# PX4FMUv2_4_6_6.net
KiCad netlist of a schematic drawn in Altium Designer
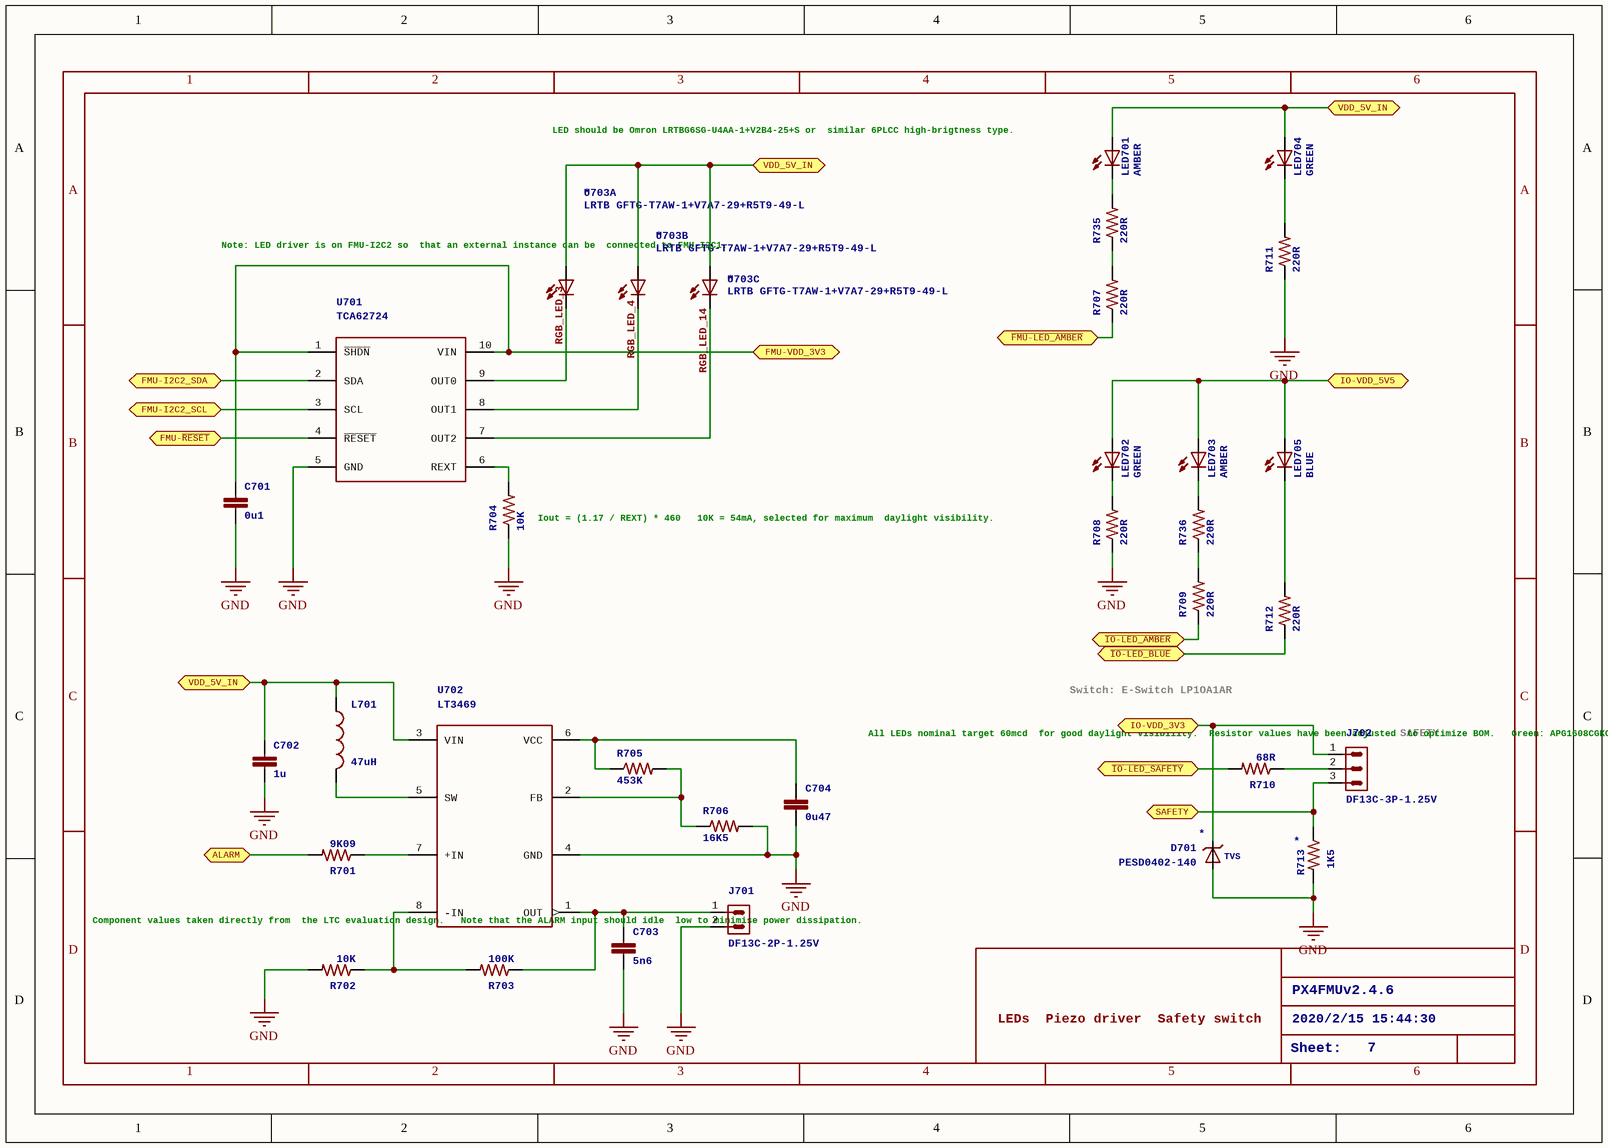
[diagram p0: PX4FMUv2.4.6_6.SchDoc]

(export (version "E")
  (design (tool "Eeschema 10.0.6"))
  (components
    (comp (ref "C701")
      (value "0u1")
      (footprint "0402-CAP")
      (description "CapacitorStandard 0603 ceramic capacitor, and 0.1\" leaded capacitor.")
      (fields (field (name "PARTNO") "CC0402ZRY5V7BB104"))
      (libsource (lib "pixhawk2") (part "CAP0402"))
    )
    (comp (ref "C702")
      (value "1u")
      (footprint "0603-CAP")
      (description "CapacitorStandard 0603 ceramic capacitor, and 0.1\" leaded capacitor.")
      (fields (field (name "PARTNO") "CC0603ZRY5V7BB105"))
      (libsource (lib "pixhawk2") (part "CAP0603"))
    )
    (comp (ref "C703")
      (value "5n6")
      (footprint "0402-CAP")
      (description "CapacitorStandard 0603 ceramic capacitor, and 0.1\" leaded capacitor.")
      (fields (field (name "PARTNO") "C0402C562K5RACTU"))
      (libsource (lib "pixhawk2") (part "CAP0402"))
    )
    (comp (ref "C704")
      (value "0u47")
      (footprint "0402-CAP")
      (description "CapacitorStandard 0603 ceramic capacitor, and 0.1\" leaded capacitor.")
      (fields (field (name "PARTNO") "C1005X5R1C474K050BC"))
      (libsource (lib "pixhawk2") (part "CAP0402"))
    )
    (comp (ref "D701")
      (value "PESD0402-140")
      (footprint "0402-TVS")
      (fields (field (name "NAME") "*") (field (name "TVS") "TVS"))
      (libsource (lib "pixhawk2") (part "DIODE-TVS"))
    )
    (comp (ref "J701")
      (value "DF13C-2P-1.25V")
      (footprint "DF13C-2P-1.25V")
      (description "DF13-2P 1.25mm Pitch Miniature Crimping Connector.")
      (fields (field (name "PARTNO") "DF13C-2P-1.25V(20)") (field (name "LIBRARYNAME") "con-hirose-df13"))
      (libsource (lib "con-hirose-df13") (part "DF13-2P-1.25V"))
    )
    (comp (ref "J702")
      (value "DF13C-3P-1.25V")
      (footprint "DF13C-3P-1.25V")
      (description "DF13-3P 1.25mm Pitch Miniature Crimping Connector.")
      (fields (field (name "PARTNO") "DF13C-3P-1.25V(20)") (field (name "LIBRARYNAME") "con-hirose-df13"))
      (libsource (lib "con-hirose-df13") (part "DF13-3P-1.25V"))
    )
    (comp (ref "L701")
      (value "47uH")
      (footprint "0805-IND")
      (fields (field (name "PARTNO") "MLZ2012M470W"))
      (libsource (lib "pixhawk2") (part "INDUCTOR0805"))
    )
    (comp (ref "LED701")
      (value "AMBER")
      (footprint "0603-LED")
      (fields (field (name "PARTNO") "APTD1608SECK"))
      (libsource (lib "pixhawk2") (part "LED0603"))
    )
    (comp (ref "LED702")
      (value "GREEN")
      (footprint "0603-LED")
      (fields (field (name "PARTNO") "APTD1608CGCK"))
      (libsource (lib "pixhawk2") (part "LED0603"))
    )
    (comp (ref "LED703")
      (value "AMBER")
      (footprint "0603-LED")
      (fields (field (name "PARTNO") "APTD1608SECK"))
      (libsource (lib "pixhawk2") (part "LED0603"))
    )
    (comp (ref "LED704")
      (value "GREEN")
      (footprint "0603-LED")
      (fields (field (name "PARTNO") "APTD1608CGCK"))
      (libsource (lib "pixhawk2") (part "LED0603"))
    )
    (comp (ref "LED705")
      (value "BLUE")
      (footprint "0603-LED")
      (fields (field (name "PARTNO") "APTD1608QBC/D"))
      (libsource (lib "pixhawk2") (part "LED0603"))
    )
    (comp (ref "R701")
      (value "9K09")
      (footprint "0402-RES")
      (fields (field (name "PARTNO") "RMCF0402FT9K09"))
      (libsource (lib "pixhawk2") (part "RESISTOR0402-RES"))
    )
    (comp (ref "R702")
      (value "10K")
      (footprint "0402-RES")
      (fields (field (name "PARTNO") "RC0402FR-0710KL"))
      (libsource (lib "pixhawk2") (part "RESISTOR0402-RES"))
    )
    (comp (ref "R703")
      (value "100K")
      (footprint "0402-RES")
      (fields (field (name "PARTNO") "RC0402FR-07100KL"))
      (libsource (lib "pixhawk2") (part "RESISTOR0402-RES"))
    )
    (comp (ref "R704")
      (value "10K")
      (footprint "0402-RES")
      (fields (field (name "PARTNO") "RC0402FR-0710KL"))
      (libsource (lib "pixhawk2") (part "RESISTOR0402-RES"))
    )
    (comp (ref "R705")
      (value "453K")
      (footprint "0402-RES")
      (fields (field (name "PARTNO") "RMCF0402FT453K"))
      (libsource (lib "pixhawk2") (part "RESISTOR0402-RES"))
    )
    (comp (ref "R706")
      (value "16K5")
      (footprint "0402-RES")
      (fields (field (name "PARTNO") "RMCF0402FT16K5"))
      (libsource (lib "pixhawk2") (part "RESISTOR0402-RES"))
    )
    (comp (ref "R707")
      (value "220R")
      (footprint "0402-RES")
      (fields (field (name "PARTNO") "RC0402FR-07220RL"))
      (libsource (lib "pixhawk2") (part "RESISTOR0402-RES"))
    )
    (comp (ref "R708")
      (value "220R")
      (footprint "0402-RES")
      (fields (field (name "PARTNO") "RC0402FR-07220RL"))
      (libsource (lib "pixhawk2") (part "RESISTOR0402-RES"))
    )
    (comp (ref "R709")
      (value "220R")
      (footprint "0402-RES")
      (fields (field (name "PARTNO") "RC0402FR-07220RL"))
      (libsource (lib "pixhawk2") (part "RESISTOR0402-RES"))
    )
    (comp (ref "R710")
      (value "68R")
      (footprint "0402-RES")
      (fields (field (name "PARTNO") "ERJ-2GEJ680X"))
      (libsource (lib "pixhawk2") (part "RESISTOR0402-RES"))
    )
    (comp (ref "R711")
      (value "220R")
      (footprint "0402-RES")
      (fields (field (name "PARTNO") "RC0402FR-07220RL"))
      (libsource (lib "pixhawk2") (part "RESISTOR0402-RES"))
    )
    (comp (ref "R712")
      (value "220R")
      (footprint "0402-RES")
      (fields (field (name "PARTNO") "RC0402FR-07220RL"))
      (libsource (lib "pixhawk2") (part "RESISTOR0402-RES"))
    )
    (comp (ref "R713")
      (value "1K5")
      (footprint "0402-RES")
      (fields (field (name "NAME") "*") (field (name "PARTNO") "RC0402FR-071K5L"))
      (libsource (lib "pixhawk2") (part "RESISTOR0402-RES"))
    )
    (comp (ref "R735")
      (value "220R")
      (footprint "0402-RES")
      (fields (field (name "PARTNO") "RC0402FR-07220RL"))
      (libsource (lib "pixhawk2") (part "RESISTOR0402-RES"))
    )
    (comp (ref "R736")
      (value "220R")
      (footprint "0402-RES")
      (fields (field (name "PARTNO") "RC0402FR-07220RL"))
      (libsource (lib "pixhawk2") (part "RESISTOR0402-RES"))
    )
    (comp (ref "U701")
      (value "TCA62724FMG")
      (footprint "SON10")
      (description "Toshiba TCA62724FMG I2C RGB LED driver")
      (fields (field (name "TCA62724") "TCA62724"))
      (libsource (lib "pixhawk2") (part "TCA62724FMG"))
    )
    (comp (ref "U702")
      (value "LT3469")
      (footprint "SOT23-8")
      (description "LT3469 Piezo microactuator driver with boost regulator")
      (fields (field (name "PARTNO") "LT3469ETS8"))
      (libsource (lib "pixhawk2") (part "LT3469"))
    )
    (comp (ref "U703")
      (value "LRTB GFTG-T7AW-1+V7A7-29+R5T9-49-L")
      (footprint "6-PLCC")
      (description "RGB LED with separate anode/cathode terminals")
      (fields (field (name "NAME") "*"))
      (libsource (lib "pixhawk2") (part "RGB-LED6-PLCC"))
    )
  )
  (nets
    (net (code "1") (name "/ALARM") (class "Default")
      (node (ref "R701") (pin "P$2") (pinfunction "2_P$2") (pintype "passive"))
    )
    (net (code "2") (name "/FMU-I2C2_SCL") (class "Default")
      (node (ref "U701") (pin "3") (pinfunction "SCL_3") (pintype "passive"))
    )
    (net (code "3") (name "/FMU-I2C2_SDA") (class "Default")
      (node (ref "U701") (pin "2") (pinfunction "SDA_2") (pintype "passive"))
    )
    (net (code "4") (name "/FMU-VDD_3V3") (class "Default")
      (node (ref "C701") (pin "P$1") (pinfunction "1_P$1") (pintype "passive"))
      (node (ref "U701") (pin "1") (pinfunction "~{SHDN}_1") (pintype "passive"))
      (node (ref "U701") (pin "10") (pinfunction "VIN_10") (pintype "power_in"))
    )
    (net (code "5") (name "/FMU-~{RESET}") (class "Default")
      (node (ref "U701") (pin "4") (pinfunction "~{RESET}_4") (pintype "passive"))
    )
    (net (code "6") (name "/IO-VDD_3V3") (class "Default")
      (node (ref "D701") (pin "C") (pinfunction "C_C") (pintype "passive"))
      (node (ref "J702") (pin "1") (pinfunction "1_1") (pintype "passive"))
    )
    (net (code "7") (name "/IO-VDD_5V5") (class "Default")
      (node (ref "LED702") (pin "A") (pinfunction "A_A") (pintype "passive"))
      (node (ref "LED703") (pin "A") (pinfunction "A_A") (pintype "passive"))
      (node (ref "LED705") (pin "A") (pinfunction "A_A") (pintype "passive"))
    )
    (net (code "8") (name "/RGB_LED_3") (class "Default")
      (node (ref "U701") (pin "9") (pinfunction "OUT0_9") (pintype "open_collector"))
      (node (ref "U703") (pin "C1") (pinfunction "C_C1") (pintype "passive"))
    )
    (net (code "9") (name "/RGB_LED_4") (class "Default")
      (node (ref "U701") (pin "8") (pinfunction "OUT1_8") (pintype "open_collector"))
      (node (ref "U703") (pin "C2") (pinfunction "C_C2") (pintype "passive"))
    )
    (net (code "10") (name "/RGB_LED_14") (class "Default")
      (node (ref "U701") (pin "7") (pinfunction "OUT2_7") (pintype "open_collector"))
      (node (ref "U703") (pin "C3") (pinfunction "C_C3") (pintype "passive"))
    )
    (net (code "11") (name "/SAFETY") (class "Default")
      (node (ref "J702") (pin "3") (pinfunction "3_3") (pintype "passive"))
      (node (ref "R713") (pin "P$1") (pinfunction "1_P$1") (pintype "passive"))
    )
    (net (code "12") (name "/VDD_5V_IN") (class "Default")
      (node (ref "C702") (pin "P$1") (pinfunction "1_P$1") (pintype "passive"))
      (node (ref "L701") (pin "P$1") (pinfunction "1_P$1") (pintype "passive"))
      (node (ref "LED701") (pin "A") (pinfunction "A_A") (pintype "passive"))
      (node (ref "LED704") (pin "A") (pinfunction "A_A") (pintype "passive"))
      (node (ref "U702") (pin "3") (pinfunction "VIN_3") (pintype "power_in"))
      (node (ref "U703") (pin "A1") (pinfunction "A_A1") (pintype "passive"))
      (node (ref "U703") (pin "A2") (pinfunction "A_A2") (pintype "passive"))
      (node (ref "U703") (pin "A3") (pinfunction "A_A3") (pintype "passive"))
    )
    (net (code "13") (name "/~{FMU-LED_AMBER}") (class "Default")
      (node (ref "R707") (pin "P$1") (pinfunction "1_P$1") (pintype "passive"))
    )
    (net (code "14") (name "/~{IO-LED_AMBER}") (class "Default")
      (node (ref "R709") (pin "P$1") (pinfunction "1_P$1") (pintype "passive"))
    )
    (net (code "15") (name "/~{IO-LED_BLUE}") (class "Default")
      (node (ref "R712") (pin "P$1") (pinfunction "1_P$1") (pintype "passive"))
    )
    (net (code "16") (name "/~{IO-LED_SAFETY}") (class "Default")
      (node (ref "R710") (pin "P$2") (pinfunction "2_P$2") (pintype "passive"))
    )
    (net (code "17") (name "GND") (class "Default")
      (node (ref "C701") (pin "P$2") (pinfunction "2_P$2") (pintype "passive"))
      (node (ref "C702") (pin "P$2") (pinfunction "2_P$2") (pintype "passive"))
      (node (ref "C703") (pin "P$2") (pinfunction "2_P$2") (pintype "passive"))
      (node (ref "C704") (pin "P$2") (pinfunction "2_P$2") (pintype "passive"))
      (node (ref "D701") (pin "A") (pinfunction "A_A") (pintype "passive"))
      (node (ref "J701") (pin "2") (pinfunction "2_2") (pintype "passive"))
      (node (ref "R702") (pin "P$2") (pinfunction "2_P$2") (pintype "passive"))
      (node (ref "R704") (pin "P$1") (pinfunction "1_P$1") (pintype "passive"))
      (node (ref "R706") (pin "P$2") (pinfunction "2_P$2") (pintype "passive"))
      (node (ref "R708") (pin "P$1") (pinfunction "1_P$1") (pintype "passive"))
      (node (ref "R711") (pin "P$1") (pinfunction "1_P$1") (pintype "passive"))
      (node (ref "R713") (pin "P$2") (pinfunction "2_P$2") (pintype "passive"))
      (node (ref "U701") (pin "5") (pinfunction "GND_5") (pintype "power_in"))
      (node (ref "U702") (pin "4") (pinfunction "GND_4") (pintype "power_in"))
    )
    (net (code "18") (name "Net-(C703-1)") (class "Default")
      (node (ref "C703") (pin "P$1") (pinfunction "1_P$1") (pintype "passive"))
      (node (ref "J701") (pin "1") (pinfunction "1_1") (pintype "passive"))
      (node (ref "R703") (pin "P$1") (pinfunction "1_P$1") (pintype "passive"))
      (node (ref "U702") (pin "1") (pinfunction "OUT_1") (pintype "output"))
    )
    (net (code "19") (name "Net-(C704-1)") (class "Default")
      (node (ref "C704") (pin "P$1") (pinfunction "1_P$1") (pintype "passive"))
      (node (ref "R705") (pin "P$1") (pinfunction "1_P$1") (pintype "passive"))
      (node (ref "U702") (pin "6") (pinfunction "VCC_6") (pintype "passive"))
    )
    (net (code "20") (name "Net-(L701-2)") (class "Default")
      (node (ref "L701") (pin "P$2") (pinfunction "2_P$2") (pintype "passive"))
      (node (ref "U702") (pin "5") (pinfunction "SW_5") (pintype "passive"))
    )
    (net (code "21") (name "Net-(R701-1)") (class "Default")
      (node (ref "R701") (pin "P$1") (pinfunction "1_P$1") (pintype "passive"))
      (node (ref "U702") (pin "7") (pinfunction "+IN_7") (pintype "passive"))
    )
    (net (code "22") (name "Net-(R702-1)") (class "Default")
      (node (ref "R702") (pin "P$1") (pinfunction "1_P$1") (pintype "passive"))
      (node (ref "R703") (pin "P$2") (pinfunction "2_P$2") (pintype "passive"))
      (node (ref "U702") (pin "8") (pinfunction "-IN_8") (pintype "passive"))
    )
    (net (code "23") (name "Net-(R704-2)") (class "Default")
      (node (ref "R704") (pin "P$2") (pinfunction "2_P$2") (pintype "passive"))
      (node (ref "U701") (pin "6") (pinfunction "REXT_6") (pintype "passive"))
    )
    (net (code "24") (name "Net-(R705-2)") (class "Default")
      (node (ref "R705") (pin "P$2") (pinfunction "2_P$2") (pintype "passive"))
      (node (ref "R706") (pin "P$1") (pinfunction "1_P$1") (pintype "passive"))
      (node (ref "U702") (pin "2") (pinfunction "FB_2") (pintype "passive"))
    )
    (net (code "25") (name "Net-(R707-2)") (class "Default")
      (node (ref "R707") (pin "P$2") (pinfunction "2_P$2") (pintype "passive"))
      (node (ref "R735") (pin "P$1") (pinfunction "1_P$1") (pintype "passive"))
    )
    (net (code "26") (name "Net-(R708-2)") (class "Default")
      (node (ref "LED702") (pin "C") (pinfunction "C_C") (pintype "passive"))
      (node (ref "R708") (pin "P$2") (pinfunction "2_P$2") (pintype "passive"))
    )
    (net (code "27") (name "Net-(R709-2)") (class "Default")
      (node (ref "R709") (pin "P$2") (pinfunction "2_P$2") (pintype "passive"))
      (node (ref "R736") (pin "P$1") (pinfunction "1_P$1") (pintype "passive"))
    )
    (net (code "28") (name "Net-(R710-1)") (class "Default")
      (node (ref "J702") (pin "2") (pinfunction "2_2") (pintype "passive"))
      (node (ref "R710") (pin "P$1") (pinfunction "1_P$1") (pintype "passive"))
    )
    (net (code "29") (name "Net-(R711-2)") (class "Default")
      (node (ref "LED704") (pin "C") (pinfunction "C_C") (pintype "passive"))
      (node (ref "R711") (pin "P$2") (pinfunction "2_P$2") (pintype "passive"))
    )
    (net (code "30") (name "Net-(R712-2)") (class "Default")
      (node (ref "LED705") (pin "C") (pinfunction "C_C") (pintype "passive"))
      (node (ref "R712") (pin "P$2") (pinfunction "2_P$2") (pintype "passive"))
    )
    (net (code "31") (name "Net-(R735-2)") (class "Default")
      (node (ref "LED701") (pin "C") (pinfunction "C_C") (pintype "passive"))
      (node (ref "R735") (pin "P$2") (pinfunction "2_P$2") (pintype "passive"))
    )
    (net (code "32") (name "Net-(R736-2)") (class "Default")
      (node (ref "LED703") (pin "C") (pinfunction "C_C") (pintype "passive"))
      (node (ref "R736") (pin "P$2") (pinfunction "2_P$2") (pintype "passive"))
    )
  )
)
